# SDCARD_FLASH.net
KiCad netlist of a schematic drawn in Altium Designer
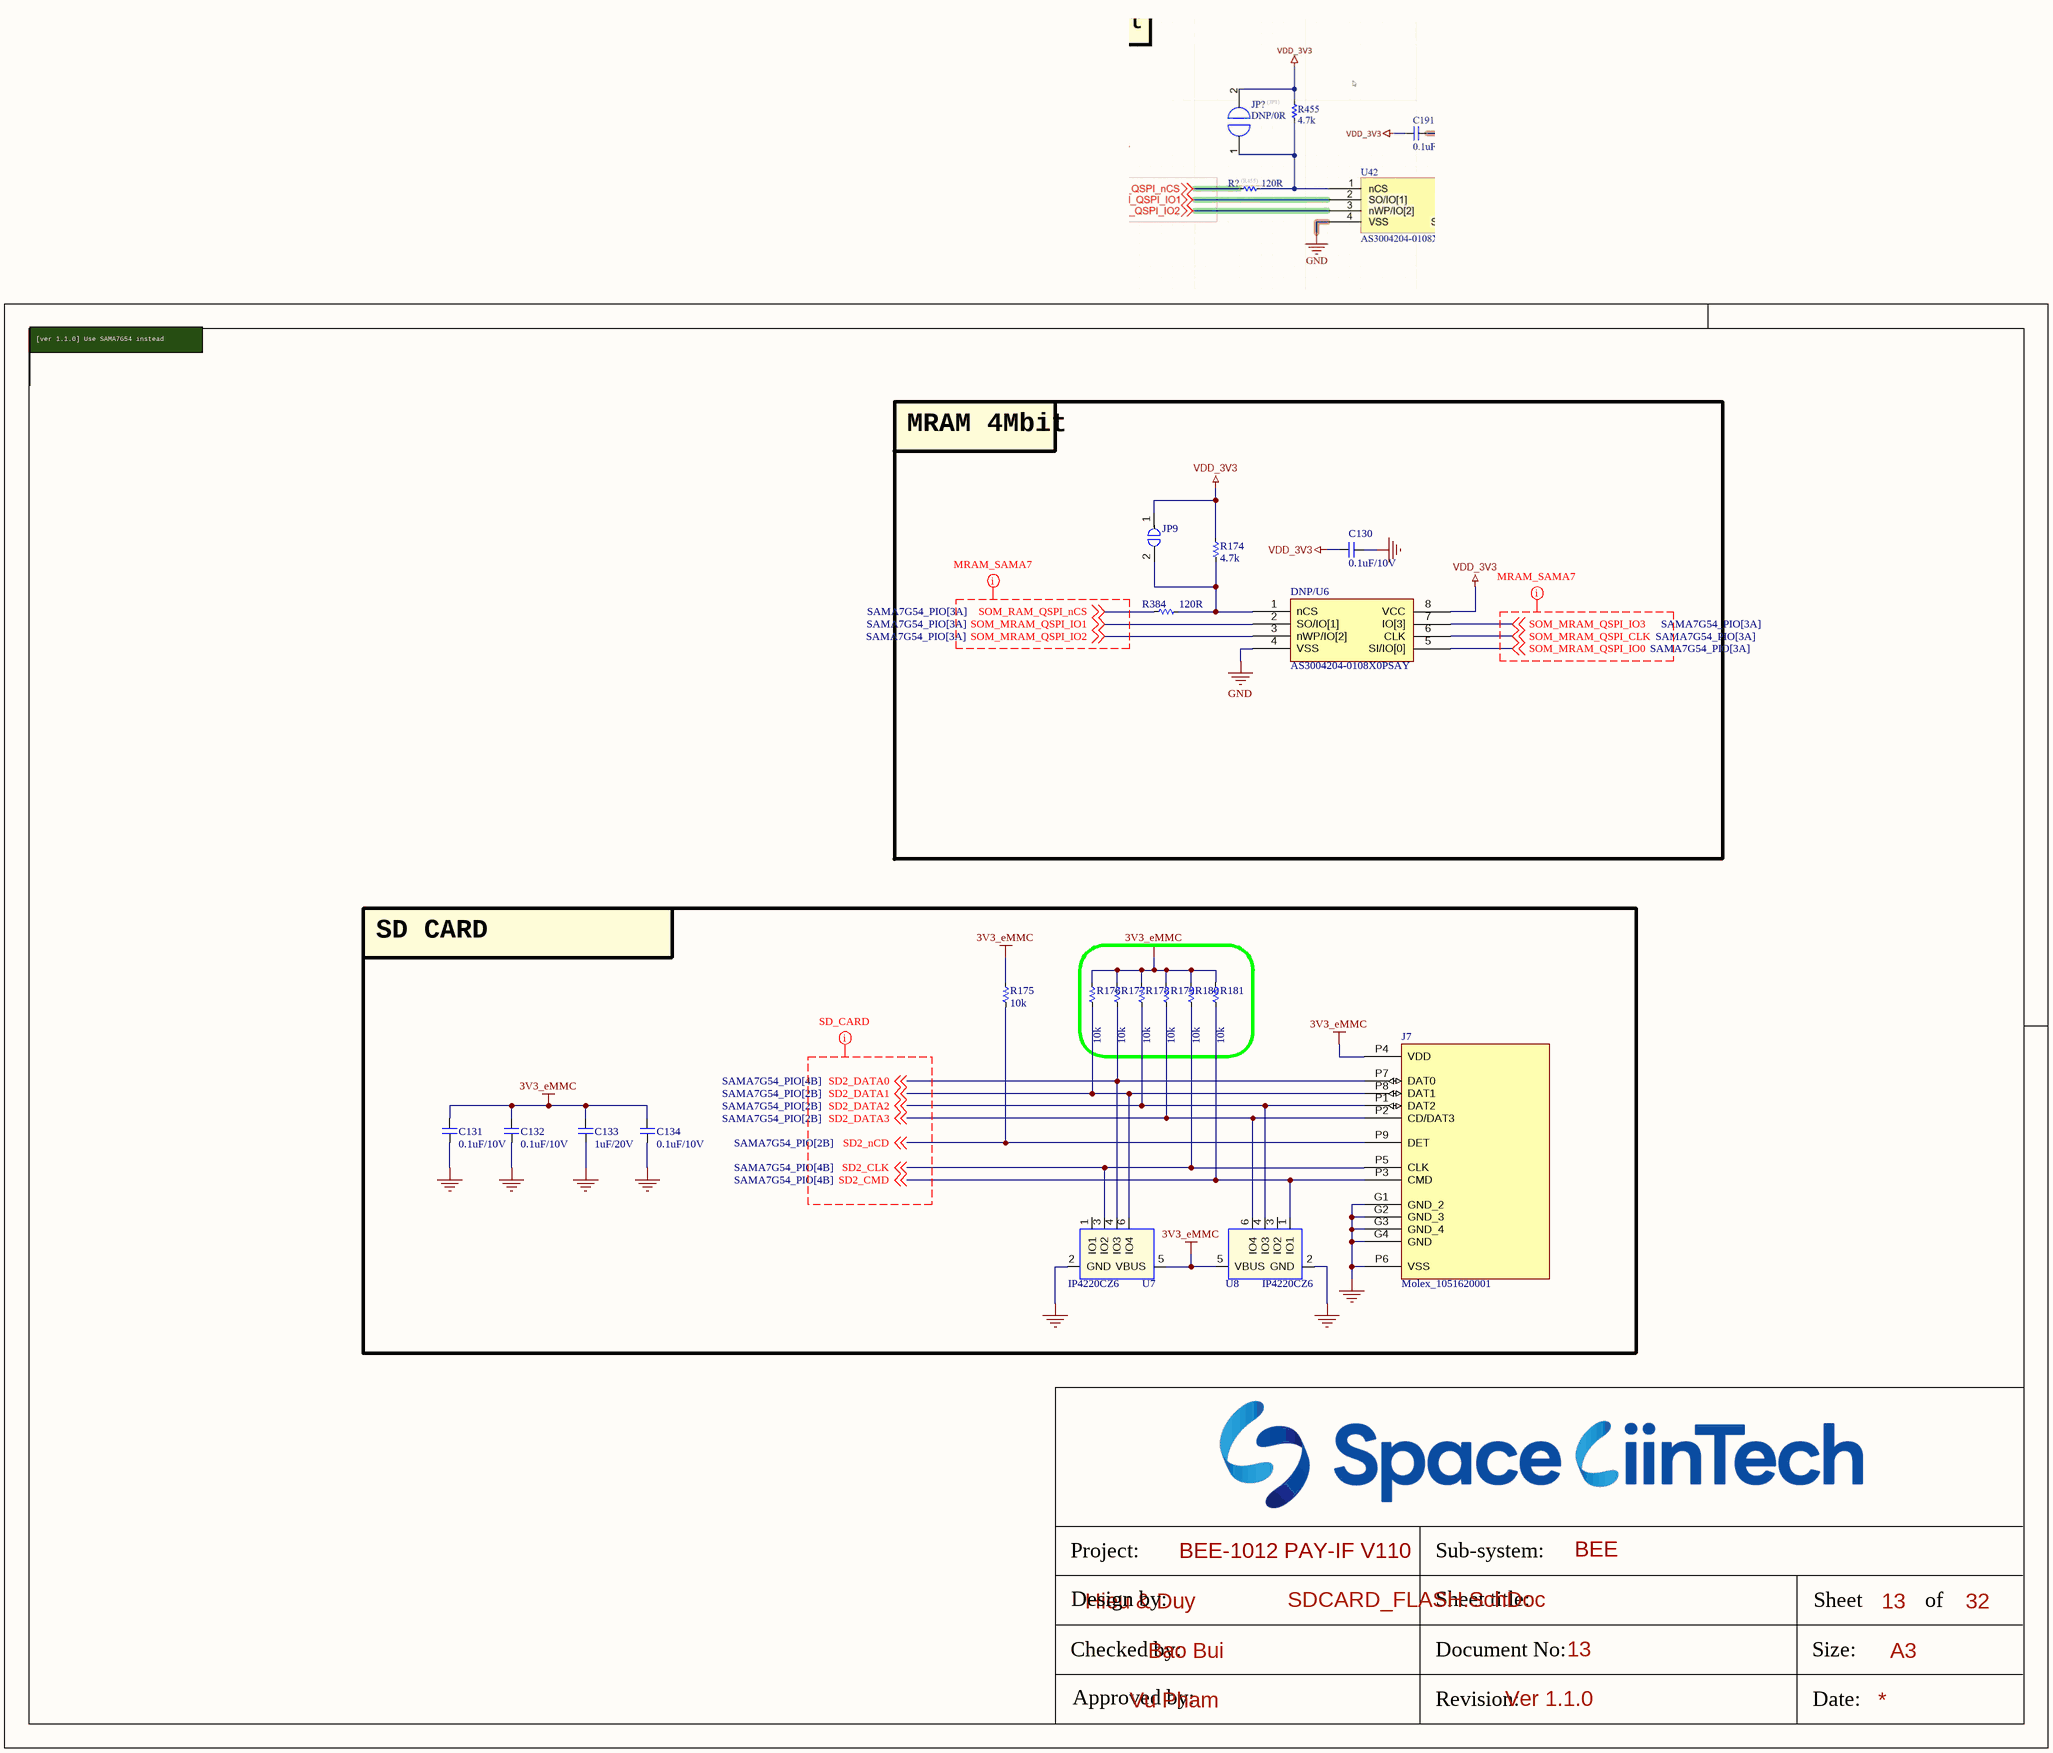
[diagram p0: SDCARD_FLASH.SchDoc]

(export (version "E")
  (design (tool "Eeschema 10.0.6"))
  (components
    (comp (ref "C130")
      (value "0.1uF/10V")
      (footprint "CAP_C_1005X50_L")
      (description "CAP")
      (libsource (lib "LABLIB") (part "_CAP_C_2"))
    )
    (comp (ref "C131")
      (value "0.1uF/10V")
      (footprint "CAP_C_1005X50_L")
      (description "CAP")
      (libsource (lib "LABLIB") (part "_CAP_C_2"))
    )
    (comp (ref "C132")
      (value "0.1uF/10V")
      (footprint "CAP_C_1005X50_L")
      (description "CAP")
      (libsource (lib "LABLIB") (part "_CAP_C_2"))
    )
    (comp (ref "C133")
      (value "1uF/20V")
      (footprint "CAP_C_1005X50_L")
      (description "CAP CHIP")
      (libsource (lib "IFBschelib") (part "_CAP_C_2"))
    )
    (comp (ref "C134")
      (value "0.1uF/10V")
      (footprint "CAP_C_1005X50_L")
      (description "CAP")
      (libsource (lib "LABLIB") (part "_CAP_C_2"))
    )
    (comp (ref "DNP/U6")
      (value "AS3004204-0108X0PSAY")
      (footprint "SOIC127P790X216-8")
      (libsource (lib "LABLIB") (part "IC_RAM_AS3004204-0108X0PSAY"))
    )
    (comp (ref "J7")
      (value "Molex_1051620001")
      (footprint "Molex_1051620001")
      (description "9 (8 + 1) Position Card Connector Secure Digital - microSDâ„¢ Surface Mount, Right Angle Gold")
      (fields (field (name "MF") "Molex") (field (name "MP") "1051620001"))
      (libsource (lib "IFBschelib") (part "Molex_1051620001"))
    )
    (comp (ref "JP9") (value "~") (footprint "JUMPER_1608") (libsource (lib "LABLIB") (part "JUMPER_1_1")))
    (comp (ref "R174")
      (value "4.7k")
      (footprint "RES_C_1005x30_L")
      (description "RES")
      (libsource (lib "IFBschelib") (part "_RES_B_2"))
    )
    (comp (ref "R175")
      (value "10k")
      (footprint "RES_C_1005x30_L")
      (description "RES")
      (libsource (lib "LABLIB") (part "_RES_B_2"))
    )
    (comp (ref "R176")
      (value "10k")
      (footprint "RES_C_1005x30_L")
      (description "RES")
      (libsource (lib "LABLIB") (part "_RES_B_2"))
    )
    (comp (ref "R177")
      (value "10k")
      (footprint "RES_C_1005x30_L")
      (description "RES")
      (libsource (lib "LABLIB") (part "_RES_B_2"))
    )
    (comp (ref "R178")
      (value "10k")
      (footprint "RES_C_1005x30_L")
      (description "RES")
      (libsource (lib "LABLIB") (part "_RES_B_2"))
    )
    (comp (ref "R179")
      (value "10k")
      (footprint "RES_C_1005x30_L")
      (description "RES")
      (libsource (lib "LABLIB") (part "_RES_B_2"))
    )
    (comp (ref "R180")
      (value "10k")
      (footprint "RES_C_1005x30_L")
      (description "RES")
      (libsource (lib "LABLIB") (part "_RES_B_2"))
    )
    (comp (ref "R181")
      (value "10k")
      (footprint "RES_C_1005x30_L")
      (description "RES")
      (libsource (lib "LABLIB") (part "_RES_B_2"))
    )
    (comp (ref "R384")
      (value "120R")
      (footprint "RES_C_1005x30_L")
      (description "RES")
      (libsource (lib "LABLIB") (part "_RES_B_2"))
    )
    (comp (ref "U7")
      (value "IP4220CZ6")
      (footprint "DIODE_SOT457_1P7X3P1_NEX")
      (libsource (lib "") (part "IP4220CZ6_0_1"))
    )
    (comp (ref "U8")
      (value "IP4220CZ6")
      (footprint "DIODE_SOT457_1P7X3P1_NEX")
      (libsource (lib "LABLIB") (part "IP4220CZ6_0"))
    )
  )
  (nets
    (net (code "1") (name "3V3_eMMC") (class "Default")
      (node (ref "C131") (pin "2") (pinfunction "2_2") (pintype "passive"))
      (node (ref "C132") (pin "2") (pinfunction "2_2") (pintype "passive"))
      (node (ref "C133") (pin "2") (pinfunction "2_2") (pintype "passive"))
      (node (ref "C134") (pin "2") (pinfunction "2_2") (pintype "passive"))
      (node (ref "J7") (pin "P4") (pinfunction "VDD_P4") (pintype "power_in"))
      (node (ref "R175") (pin "2") (pinfunction "2_2") (pintype "passive"))
      (node (ref "R176") (pin "2") (pinfunction "2_2") (pintype "passive"))
      (node (ref "R177") (pin "2") (pinfunction "2_2") (pintype "passive"))
      (node (ref "R178") (pin "2") (pinfunction "2_2") (pintype "passive"))
      (node (ref "R179") (pin "2") (pinfunction "2_2") (pintype "passive"))
      (node (ref "R180") (pin "2") (pinfunction "2_2") (pintype "passive"))
      (node (ref "R181") (pin "2") (pinfunction "2_2") (pintype "passive"))
      (node (ref "U7") (pin "5") (pinfunction "VBUS_5") (pintype "passive"))
      (node (ref "U8") (pin "5") (pinfunction "VBUS_5") (pintype "passive"))
    )
    (net (code "2") (name "GND") (class "Default")
      (node (ref "C130") (pin "1") (pinfunction "1_1") (pintype "passive"))
      (node (ref "C131") (pin "1") (pinfunction "1_1") (pintype "passive"))
      (node (ref "C132") (pin "1") (pinfunction "1_1") (pintype "passive"))
      (node (ref "C133") (pin "1") (pinfunction "1_1") (pintype "passive"))
      (node (ref "C134") (pin "1") (pinfunction "1_1") (pintype "passive"))
      (node (ref "DNP/U6") (pin "4") (pinfunction "VSS_4") (pintype "passive"))
      (node (ref "J7") (pin "G1") (pinfunction "GND_2_G1") (pintype "passive"))
      (node (ref "J7") (pin "G2") (pinfunction "GND_3_G2") (pintype "passive"))
      (node (ref "J7") (pin "G3") (pinfunction "GND_4_G3") (pintype "passive"))
      (node (ref "J7") (pin "G4") (pinfunction "GND_G4") (pintype "passive"))
      (node (ref "J7") (pin "P6") (pinfunction "VSS_P6") (pintype "passive"))
      (node (ref "U7") (pin "2") (pinfunction "GND_2") (pintype "passive"))
      (node (ref "U8") (pin "2") (pinfunction "GND_2") (pintype "passive"))
    )
    (net (code "3") (name "Net-(DNP/U6-nCS)") (class "Default")
      (node (ref "DNP/U6") (pin "1") (pinfunction "nCS_1") (pintype "passive"))
      (node (ref "JP9") (pin "2") (pinfunction "2_2") (pintype "passive"))
      (node (ref "R174") (pin "1") (pinfunction "1_1") (pintype "passive"))
      (node (ref "R384") (pin "2") (pinfunction "2_2") (pintype "passive"))
    )
    (net (code "4") (name "SD2_CLK") (class "Default")
      (node (ref "J7") (pin "P5") (pinfunction "CLK_P5") (pintype "passive"))
      (node (ref "R180") (pin "1") (pinfunction "1_1") (pintype "passive"))
      (node (ref "U7") (pin "3") (pinfunction "IO2_3") (pintype "passive"))
    )
    (net (code "5") (name "SD2_CMD") (class "Default")
      (node (ref "J7") (pin "P3") (pinfunction "CMD_P3") (pintype "passive"))
      (node (ref "R181") (pin "1") (pinfunction "1_1") (pintype "passive"))
      (node (ref "U8") (pin "1") (pinfunction "IO1_1") (pintype "passive"))
    )
    (net (code "6") (name "SD2_DATA0") (class "Default")
      (node (ref "J7") (pin "P7") (pinfunction "DAT0_P7") (pintype "bidirectional"))
      (node (ref "R177") (pin "1") (pinfunction "1_1") (pintype "passive"))
      (node (ref "U7") (pin "4") (pinfunction "IO3_4") (pintype "passive"))
    )
    (net (code "7") (name "SD2_DATA1") (class "Default")
      (node (ref "J7") (pin "P8") (pinfunction "DAT1_P8") (pintype "bidirectional"))
      (node (ref "R176") (pin "1") (pinfunction "1_1") (pintype "passive"))
      (node (ref "U7") (pin "6") (pinfunction "IO4_6") (pintype "passive"))
    )
    (net (code "8") (name "SD2_DATA2") (class "Default")
      (node (ref "J7") (pin "P1") (pinfunction "DAT2_P1") (pintype "bidirectional"))
      (node (ref "R178") (pin "1") (pinfunction "1_1") (pintype "passive"))
      (node (ref "U8") (pin "4") (pinfunction "IO3_4") (pintype "passive"))
    )
    (net (code "9") (name "SD2_DATA3") (class "Default")
      (node (ref "J7") (pin "P2") (pinfunction "CD/DAT3_P2") (pintype "passive"))
      (node (ref "R179") (pin "1") (pinfunction "1_1") (pintype "passive"))
      (node (ref "U8") (pin "6") (pinfunction "IO4_6") (pintype "passive"))
    )
    (net (code "10") (name "SD2_nCD") (class "Default")
      (node (ref "J7") (pin "P9") (pinfunction "DET_P9") (pintype "passive"))
      (node (ref "R175") (pin "1") (pinfunction "1_1") (pintype "passive"))
    )
    (net (code "11") (name "SOM_MRAM_QSPI_CLK") (class "Default")
      (node (ref "DNP/U6") (pin "6") (pinfunction "CLK_6") (pintype "passive"))
    )
    (net (code "12") (name "SOM_MRAM_QSPI_IO0") (class "Default")
      (node (ref "DNP/U6") (pin "5") (pinfunction "SI/IO[0]_5") (pintype "passive"))
    )
    (net (code "13") (name "SOM_MRAM_QSPI_IO1") (class "Default")
      (node (ref "DNP/U6") (pin "2") (pinfunction "SO/IO[1]_2") (pintype "passive"))
    )
    (net (code "14") (name "SOM_MRAM_QSPI_IO2") (class "Default")
      (node (ref "DNP/U6") (pin "3") (pinfunction "nWP/IO[2]_3") (pintype "passive"))
    )
    (net (code "15") (name "SOM_MRAM_QSPI_IO3") (class "Default")
      (node (ref "DNP/U6") (pin "7") (pinfunction "IO[3]_7") (pintype "passive"))
    )
    (net (code "16") (name "SOM_RAM_QSPI_nCS") (class "Default")
      (node (ref "R384") (pin "1") (pinfunction "1_1") (pintype "passive"))
    )
    (net (code "17") (name "VDD_3V3") (class "Default")
      (node (ref "C130") (pin "2") (pinfunction "2_2") (pintype "passive"))
      (node (ref "DNP/U6") (pin "8") (pinfunction "VCC_8") (pintype "passive"))
      (node (ref "JP9") (pin "1") (pinfunction "1_1") (pintype "passive"))
      (node (ref "R174") (pin "2") (pinfunction "2_2") (pintype "passive"))
    )
    (net (code "18") (name "unconnected-(U7-IO1-Pad1)") (class "Default")
      (node (ref "U7") (pin "1") (pinfunction "IO1_1") (pintype "passive"))
    )
    (net (code "19") (name "unconnected-(U8-IO2-Pad3)") (class "Default")
      (node (ref "U8") (pin "3") (pinfunction "IO2_3") (pintype "passive"))
    )
  )
)
